# Sheet1.net
KiCad netlist of a schematic drawn in Altium Designer
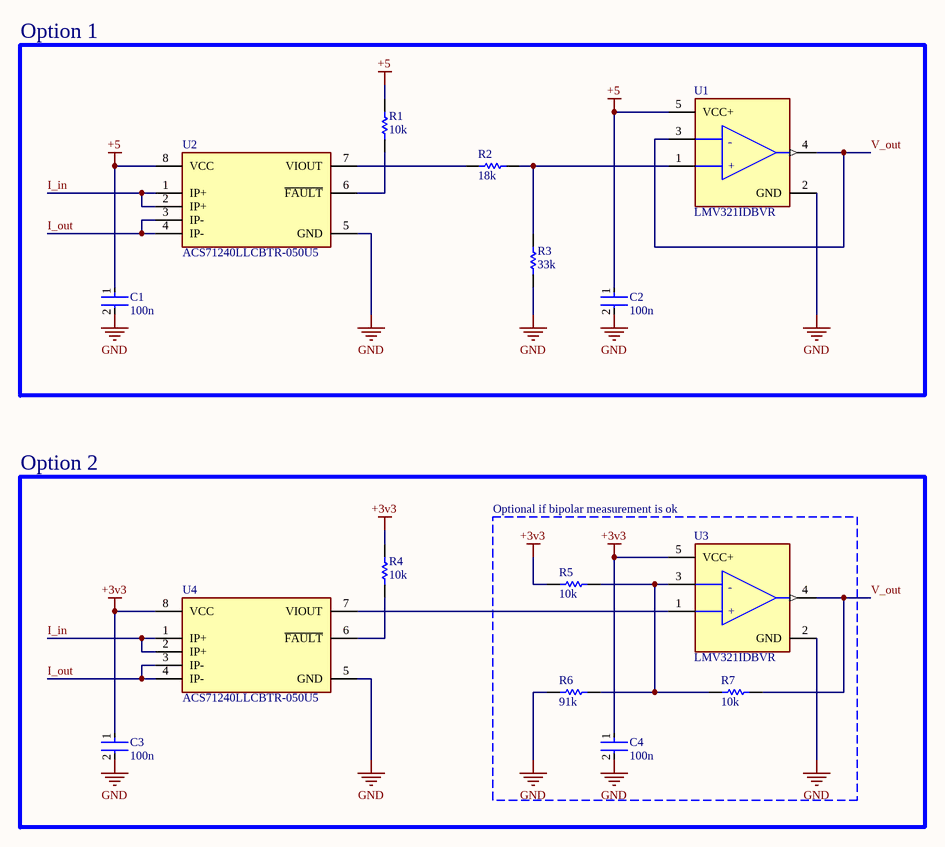
[diagram p0: Sheet1.SchDoc]

(export (version "E")
  (design (tool "Eeschema 10.0.6"))
  (components
    (comp (ref "C1")
      (value "100n")
      (footprint "FP-0402B104K500CT-IPC_C")
      (description "CAP CER 0.1UF 50V X7R 0402")
      (fields (field (name "TOLERANCE") "10%"))
      (libsource (lib "Altium Content Vault") (part "11868f565c42a9108669ba33697ecf6"))
    )
    (comp (ref "C2")
      (value "100n")
      (footprint "FP-0402B104K500CT-IPC_C")
      (description "CAP CER 0.1UF 50V X7R 0402")
      (fields (field (name "TOLERANCE") "10%"))
      (libsource (lib "Altium Content Vault") (part "11868f565c42a9108669ba33697ecf6"))
    )
    (comp (ref "C3")
      (value "100n")
      (footprint "FP-0402B104K500CT-IPC_C")
      (description "CAP CER 0.1UF 50V X7R 0402")
      (fields (field (name "TOLERANCE") "10%"))
      (libsource (lib "Altium Content Vault") (part "11868f565c42a9108669ba33697ecf6"))
    )
    (comp (ref "C4")
      (value "100n")
      (footprint "FP-0402B104K500CT-IPC_C")
      (description "CAP CER 0.1UF 50V X7R 0402")
      (fields (field (name "TOLERANCE") "10%"))
      (libsource (lib "Altium Content Vault") (part "11868f565c42a9108669ba33697ecf6"))
    )
    (comp (ref "R1")
      (value "10k")
      (footprint "RESC1609X50X30NL8T20")
      (description "Chip Resistor, 10 KOhm, +/- 1%, 100 mW, -55 to 155 degC, 0603 (1608 Metric), RoHS, Tape and Reel")
      (fields (field (name "MANUFACTURER") "Vishay Semiconductor"))
      (libsource (lib "Altium Content Vault") (part "RES-2"))
    )
    (comp (ref "R2")
      (value "18k")
      (footprint "RESC1609X50X30NL8T20")
      (description "Chip Resistor, 10 KOhm, +/- 1%, 100 mW, -55 to 155 degC, 0603 (1608 Metric), RoHS, Tape and Reel")
      (fields (field (name "MANUFACTURER") "Vishay Semiconductor"))
      (libsource (lib "Altium Content Vault") (part "RES-2"))
    )
    (comp (ref "R3")
      (value "33k")
      (footprint "RESC1609X50X30NL8T20")
      (description "Chip Resistor, 10 KOhm, +/- 1%, 100 mW, -55 to 155 degC, 0603 (1608 Metric), RoHS, Tape and Reel")
      (fields (field (name "MANUFACTURER") "Vishay Semiconductor"))
      (libsource (lib "Altium Content Vault") (part "RES-2"))
    )
    (comp (ref "R4")
      (value "10k")
      (footprint "RESC1609X50X30NL8T20")
      (description "Chip Resistor, 10 KOhm, +/- 1%, 100 mW, -55 to 155 degC, 0603 (1608 Metric), RoHS, Tape and Reel")
      (fields (field (name "MANUFACTURER") "Vishay Semiconductor"))
      (libsource (lib "Altium Content Vault") (part "RES-2"))
    )
    (comp (ref "R5")
      (value "10k")
      (footprint "RESC1609X50X30NL8T20")
      (description "Chip Resistor, 10 KOhm, +/- 1%, 100 mW, -55 to 155 degC, 0603 (1608 Metric), RoHS, Tape and Reel")
      (fields (field (name "MANUFACTURER") "Vishay Semiconductor"))
      (libsource (lib "Altium Content Vault") (part "RES-2"))
    )
    (comp (ref "R6")
      (value "91k")
      (footprint "RESC1609X50X30NL8T20")
      (description "Chip Resistor, 10 KOhm, +/- 1%, 100 mW, -55 to 155 degC, 0603 (1608 Metric), RoHS, Tape and Reel")
      (fields (field (name "MANUFACTURER") "Vishay Semiconductor"))
      (libsource (lib "Altium Content Vault") (part "RES-2"))
    )
    (comp (ref "R7")
      (value "10k")
      (footprint "RESC1609X50X30NL8T20")
      (description "Chip Resistor, 10 KOhm, +/- 1%, 100 mW, -55 to 155 degC, 0603 (1608 Metric), RoHS, Tape and Reel")
      (fields (field (name "MANUFACTURER") "Vishay Semiconductor"))
      (libsource (lib "Altium Content Vault") (part "RES-2"))
    )
    (comp (ref "U1")
      (value "LMV321IDBVR")
      (footprint "FP-DBV0005A-MFG")
      (description "IC OPAMP GP 1 CIRCUIT SOT23-5")
      (fields
        (field (name "MANUFACTURER") "Texas Instruments")
        (field (name "OCTOPART") "https://octopart.com/lmv321idbvr-texas+instruments-410381")
      )
      (libsource (lib "Altium Content Vault") (part "ec165d7f6fd2c1e6935a66fb0025aed"))
    )
    (comp (ref "U2")
      (value "ACS71240LLCBTR-050U5")
      (footprint "FP-LCB-8-MFG")
      (description "AUTOMOTIVE-GRADE, GALVANICALLY I")
      (libsource (lib "Altium Content Vault") (part "99af5cecb20feac26b47066b294b235"))
    )
    (comp (ref "U3")
      (value "LMV321IDBVR")
      (footprint "FP-DBV0005A-MFG")
      (description "IC OPAMP GP 1 CIRCUIT SOT23-5")
      (fields
        (field (name "MANUFACTURER") "Texas Instruments")
        (field (name "OCTOPART") "https://octopart.com/lmv321idbvr-texas+instruments-410381")
      )
      (libsource (lib "Altium Content Vault") (part "ec165d7f6fd2c1e6935a66fb0025aed"))
    )
    (comp (ref "U4")
      (value "ACS71240LLCBTR-050U5")
      (footprint "FP-LCB-8-MFG")
      (description "AUTOMOTIVE-GRADE, GALVANICALLY I")
      (libsource (lib "Altium Content Vault") (part "99af5cecb20feac26b47066b294b235"))
    )
  )
  (nets
    (net (code "1") (name "+3v3") (class "Default")
      (node (ref "C3") (pin "1") (pinfunction "1_1") (pintype "passive"))
      (node (ref "C4") (pin "1") (pinfunction "1_1") (pintype "passive"))
      (node (ref "R4") (pin "2") (pinfunction "2_2") (pintype "passive"))
      (node (ref "R5") (pin "2") (pinfunction "2_2") (pintype "passive"))
      (node (ref "U3") (pin "5") (pinfunction "VCC+_5") (pintype "power_in"))
      (node (ref "U4") (pin "8") (pinfunction "VCC_8") (pintype "passive"))
    )
    (net (code "2") (name "+5") (class "Default")
      (node (ref "C1") (pin "1") (pinfunction "1_1") (pintype "passive"))
      (node (ref "C2") (pin "1") (pinfunction "1_1") (pintype "passive"))
      (node (ref "R1") (pin "2") (pinfunction "2_2") (pintype "passive"))
      (node (ref "U1") (pin "5") (pinfunction "VCC+_5") (pintype "power_in"))
      (node (ref "U2") (pin "8") (pinfunction "VCC_8") (pintype "passive"))
    )
    (net (code "3") (name "/I_in") (class "Default")
      (node (ref "U2") (pin "1") (pinfunction "IP+_1") (pintype "passive"))
      (node (ref "U2") (pin "2") (pinfunction "IP+_2") (pintype "passive"))
      (node (ref "U4") (pin "1") (pinfunction "IP+_1") (pintype "passive"))
      (node (ref "U4") (pin "2") (pinfunction "IP+_2") (pintype "passive"))
    )
    (net (code "4") (name "/I_out") (class "Default")
      (node (ref "U2") (pin "3") (pinfunction "IP-_3") (pintype "passive"))
      (node (ref "U2") (pin "4") (pinfunction "IP-_4") (pintype "passive"))
      (node (ref "U4") (pin "3") (pinfunction "IP-_3") (pintype "passive"))
      (node (ref "U4") (pin "4") (pinfunction "IP-_4") (pintype "passive"))
    )
    (net (code "5") (name "/V_out") (class "Default")
      (node (ref "R7") (pin "1") (pinfunction "1_1") (pintype "passive"))
      (node (ref "U1") (pin "3") (pinfunction "1IN-_3") (pintype "tri_state"))
      (node (ref "U1") (pin "4") (pinfunction "OUT_4") (pintype "output"))
      (node (ref "U3") (pin "4") (pinfunction "OUT_4") (pintype "output"))
    )
    (net (code "6") (name "GND") (class "Default")
      (node (ref "C1") (pin "2") (pinfunction "2_2") (pintype "passive"))
      (node (ref "C2") (pin "2") (pinfunction "2_2") (pintype "passive"))
      (node (ref "C3") (pin "2") (pinfunction "2_2") (pintype "passive"))
      (node (ref "C4") (pin "2") (pinfunction "2_2") (pintype "passive"))
      (node (ref "R3") (pin "1") (pinfunction "1_1") (pintype "passive"))
      (node (ref "R6") (pin "2") (pinfunction "2_2") (pintype "passive"))
      (node (ref "U1") (pin "2") (pinfunction "GND_2") (pintype "power_in"))
      (node (ref "U2") (pin "5") (pinfunction "GND_5") (pintype "power_in"))
      (node (ref "U3") (pin "2") (pinfunction "GND_2") (pintype "power_in"))
      (node (ref "U4") (pin "5") (pinfunction "GND_5") (pintype "power_in"))
    )
    (net (code "7") (name "Net-(U1-1IN+)") (class "Default")
      (node (ref "R2") (pin "1") (pinfunction "1_1") (pintype "passive"))
      (node (ref "R3") (pin "2") (pinfunction "2_2") (pintype "passive"))
      (node (ref "U1") (pin "1") (pinfunction "1IN+_1") (pintype "tri_state"))
    )
    (net (code "8") (name "Net-(U2-VIOUT)") (class "Default")
      (node (ref "R2") (pin "2") (pinfunction "2_2") (pintype "passive"))
      (node (ref "U2") (pin "7") (pinfunction "VIOUT_7") (pintype "power_in"))
    )
    (net (code "9") (name "Net-(U2-~{FAULT})") (class "Default")
      (node (ref "R1") (pin "1") (pinfunction "1_1") (pintype "passive"))
      (node (ref "U2") (pin "6") (pinfunction "~{FAULT}_6") (pintype "passive"))
    )
    (net (code "10") (name "Net-(U3-1IN+)") (class "Default")
      (node (ref "U3") (pin "1") (pinfunction "1IN+_1") (pintype "tri_state"))
      (node (ref "U4") (pin "7") (pinfunction "VIOUT_7") (pintype "power_in"))
    )
    (net (code "11") (name "Net-(U3-1IN-)") (class "Default")
      (node (ref "R5") (pin "1") (pinfunction "1_1") (pintype "passive"))
      (node (ref "R6") (pin "1") (pinfunction "1_1") (pintype "passive"))
      (node (ref "R7") (pin "2") (pinfunction "2_2") (pintype "passive"))
      (node (ref "U3") (pin "3") (pinfunction "1IN-_3") (pintype "tri_state"))
    )
    (net (code "12") (name "Net-(U4-~{FAULT})") (class "Default")
      (node (ref "R4") (pin "1") (pinfunction "1_1") (pintype "passive"))
      (node (ref "U4") (pin "6") (pinfunction "~{FAULT}_6") (pintype "passive"))
    )
  )
)
